# SensorsAndActuators.net
KiCad netlist of a schematic drawn in Altium Designer
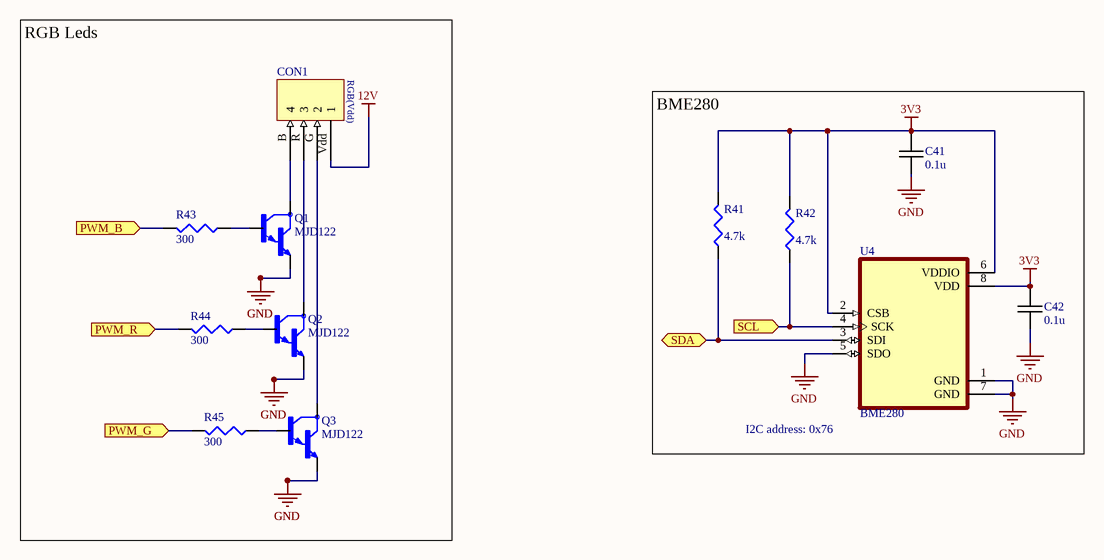
[diagram p0: SensorsAndActuators.SchDoc]

(export (version "E")
  (design (tool "Eeschema 10.0.6"))
  (components
    (comp (ref "C41")
      (value "0.1u")
      (footprint "0603C-GENERIC")
      (description "GENERIC CAPACITOR NON POLARISED 0603")
      (libsource (lib "vh_altium_library") (part "C0603-GENERIC"))
    )
    (comp (ref "C42")
      (value "0.1u")
      (footprint "0603C-GENERIC")
      (description "GENERIC CAPACITOR NON POLARISED 0603")
      (libsource (lib "vh_altium_library") (part "C0603-GENERIC"))
    )
    (comp (ref "CON1")
      (value "~")
      (footprint "PCBComponent_1")
      (libsource (lib "RGBVdd connector") (part "Component_1"))
    )
    (comp (ref "Q1")
      (value "MJD122")
      (footprint "MJD122")
      (description "Bipolar _BJT_ Transistor NPN - Darlington 100V 8A 4MHz 1.75W Surface Mount DPAK")
      (fields (field (name "MF") "ON Semiconductor"))
      (libsource (lib "LSEL_Library") (part "MJD122"))
    )
    (comp (ref "Q2")
      (value "MJD122")
      (footprint "MJD122")
      (description "Bipolar _BJT_ Transistor NPN - Darlington 100V 8A 4MHz 1.75W Surface Mount DPAK")
      (fields (field (name "MF") "ON Semiconductor"))
      (libsource (lib "LSEL_Library") (part "MJD122"))
    )
    (comp (ref "Q3")
      (value "MJD122")
      (footprint "MJD122")
      (description "Bipolar _BJT_ Transistor NPN - Darlington 100V 8A 4MHz 1.75W Surface Mount DPAK")
      (fields (field (name "MF") "ON Semiconductor"))
      (libsource (lib "LSEL_Library") (part "MJD122"))
    )
    (comp (ref "R41")
      (value "4.7k")
      (footprint "J1-0603")
      (description "Resistor")
      (fields (field (name "PUBLISHER") "Altium Limited"))
      (libsource (lib "Miscellaneous Devices") (part "Res3"))
    )
    (comp (ref "R42")
      (value "4.7k")
      (footprint "J1-0603")
      (description "Resistor")
      (fields (field (name "PUBLISHER") "Altium Limited"))
      (libsource (lib "Miscellaneous Devices") (part "Res3"))
    )
    (comp (ref "R43")
      (value "300")
      (footprint "J1-0603")
      (description "Resistor")
      (fields (field (name "PUBLISHER") "Altium Limited"))
      (libsource (lib "Miscellaneous Devices") (part "Res3"))
    )
    (comp (ref "R44")
      (value "300")
      (footprint "J1-0603")
      (description "Resistor")
      (fields (field (name "PUBLISHER") "Altium Limited"))
      (libsource (lib "Miscellaneous Devices") (part "Res3"))
    )
    (comp (ref "R45")
      (value "300")
      (footprint "J1-0603")
      (description "Resistor")
      (fields (field (name "PUBLISHER") "Altium Limited"))
      (libsource (lib "Miscellaneous Devices") (part "Res3"))
    )
    (comp (ref "U4")
      (value "BME280")
      (footprint "BME280")
      (description "Humidity Temperature Sensor 0 ~ 100% RH IÂ²C, SPI Â±3% 1s Surface Mount")
      (fields (field (name "MF") "Bosch"))
      (libsource (lib "LSEL_Library") (part "BME280"))
    )
  )
  (nets
    (net (code "1") (name "/PWM_B") (class "Default")
      (node (ref "R43") (pin "2") (pinfunction "2_2") (pintype "passive"))
    )
    (net (code "2") (name "/PWM_G") (class "Default")
      (node (ref "R45") (pin "2") (pinfunction "2_2") (pintype "passive"))
    )
    (net (code "3") (name "/PWM_R") (class "Default")
      (node (ref "R44") (pin "2") (pinfunction "2_2") (pintype "passive"))
    )
    (net (code "4") (name "/SCL") (class "Default")
      (node (ref "R42") (pin "1") (pinfunction "1_1") (pintype "passive"))
      (node (ref "U4") (pin "4") (pinfunction "SCK_4") (pintype "input"))
    )
    (net (code "5") (name "/SDA") (class "Default")
      (node (ref "R41") (pin "1") (pinfunction "1_1") (pintype "passive"))
      (node (ref "U4") (pin "3") (pinfunction "SDI_3") (pintype "bidirectional"))
    )
    (net (code "6") (name "3V3") (class "Default")
      (node (ref "C41") (pin "1") (pintype "passive"))
      (node (ref "C42") (pin "1") (pintype "passive"))
      (node (ref "R41") (pin "2") (pinfunction "2_2") (pintype "passive"))
      (node (ref "R42") (pin "2") (pinfunction "2_2") (pintype "passive"))
      (node (ref "U4") (pin "2") (pinfunction "CSB_2") (pintype "input"))
      (node (ref "U4") (pin "6") (pinfunction "VDDIO_6") (pintype "power_in"))
      (node (ref "U4") (pin "8") (pinfunction "VDD_8") (pintype "power_in"))
    )
    (net (code "7") (name "12V") (class "Default")
      (node (ref "CON1") (pin "Vdd") (pinfunction "1_Vdd") (pintype "power_in"))
    )
    (net (code "8") (name "GND") (class "Default")
      (node (ref "C41") (pin "2") (pintype "passive"))
      (node (ref "C42") (pin "2") (pintype "passive"))
      (node (ref "Q1") (pin "3") (pinfunction "E_3") (pintype "passive"))
      (node (ref "Q2") (pin "3") (pinfunction "E_3") (pintype "passive"))
      (node (ref "Q3") (pin "3") (pinfunction "E_3") (pintype "passive"))
      (node (ref "U4") (pin "1") (pinfunction "GND_1") (pintype "power_in"))
      (node (ref "U4") (pin "5") (pinfunction "SDO_5") (pintype "bidirectional"))
      (node (ref "U4") (pin "7") (pinfunction "GND_7") (pintype "power_in"))
    )
    (net (code "9") (name "Net-(CON1-2)") (class "Default")
      (node (ref "CON1") (pin "G") (pinfunction "2_G") (pintype "input"))
      (node (ref "Q3") (pin "4") (pinfunction "C_4") (pintype "passive"))
    )
    (net (code "10") (name "Net-(CON1-3)") (class "Default")
      (node (ref "CON1") (pin "R") (pinfunction "3_R") (pintype "input"))
      (node (ref "Q2") (pin "4") (pinfunction "C_4") (pintype "passive"))
    )
    (net (code "11") (name "Net-(CON1-4)") (class "Default")
      (node (ref "CON1") (pin "B") (pinfunction "4_B") (pintype "input"))
      (node (ref "Q1") (pin "4") (pinfunction "C_4") (pintype "passive"))
    )
    (net (code "12") (name "Net-(Q1-B)") (class "Default")
      (node (ref "Q1") (pin "1") (pinfunction "B_1") (pintype "passive"))
      (node (ref "R43") (pin "1") (pinfunction "1_1") (pintype "passive"))
    )
    (net (code "13") (name "Net-(Q2-B)") (class "Default")
      (node (ref "Q2") (pin "1") (pinfunction "B_1") (pintype "passive"))
      (node (ref "R44") (pin "1") (pinfunction "1_1") (pintype "passive"))
    )
    (net (code "14") (name "Net-(Q3-B)") (class "Default")
      (node (ref "Q3") (pin "1") (pinfunction "B_1") (pintype "passive"))
      (node (ref "R45") (pin "1") (pinfunction "1_1") (pintype "passive"))
    )
  )
)
